# ethero_v3.net
KiCad netlist of a schematic drawn in EAGLE
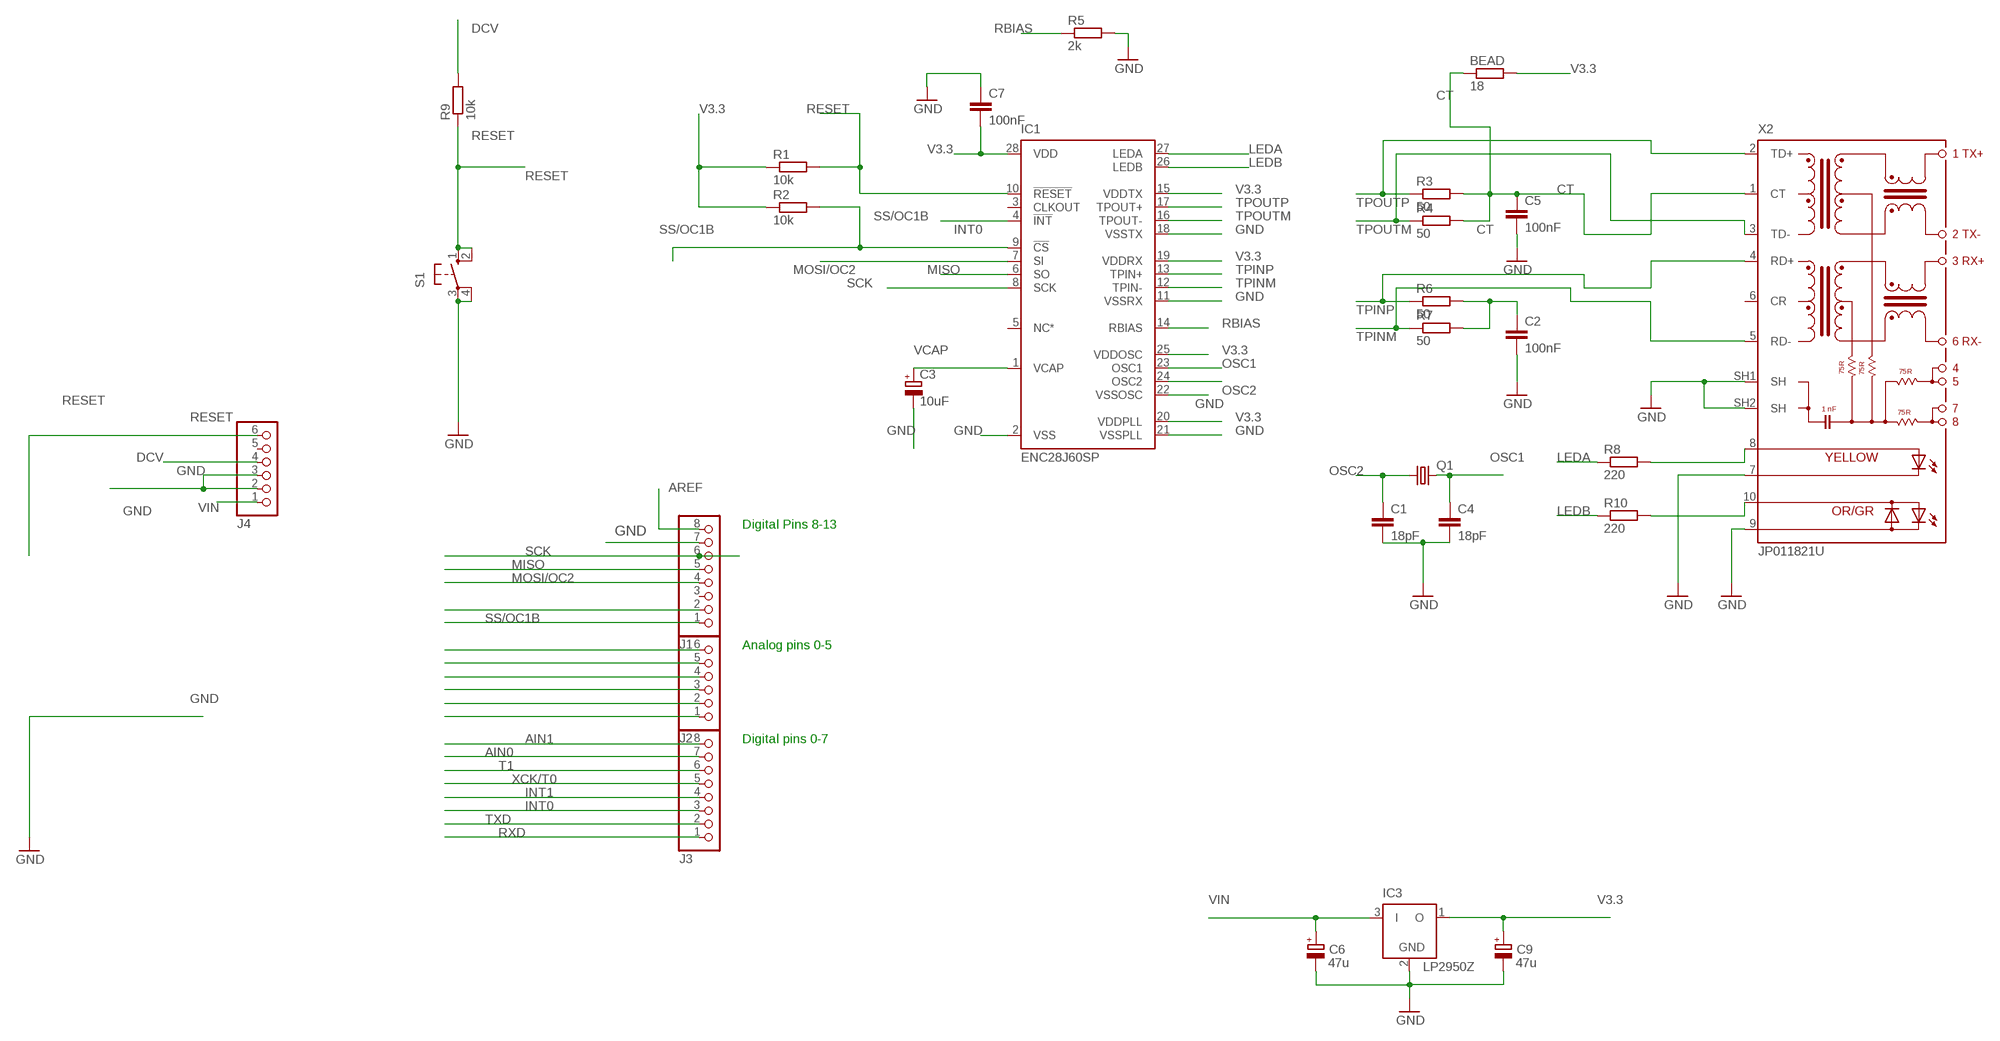
[diagram p0: schematic, sheet 1]

(export (version "E")
  (design (tool "Eeschema 10.0.6"))
  (components
    (comp (ref "BEAD")
      (value "18")
      (footprint "eagle-import:0204_7")
      (libsource (lib "eagle-import") (part "R-EU_0204/7"))
    )
    (comp (ref "C1")
      (value "18pF")
      (footprint "eagle-import:C025-025X050")
      (libsource (lib "eagle-import") (part "C-EU025-025X050"))
    )
    (comp (ref "C2")
      (value "100nF")
      (footprint "eagle-import:C025-025X050")
      (libsource (lib "eagle-import") (part "C-EU025-025X050"))
    )
    (comp (ref "C3")
      (value "10uF")
      (footprint "eagle-import:E5-5")
      (libsource (lib "eagle-import") (part "CPOL-EUE5-5"))
    )
    (comp (ref "C4")
      (value "18pF")
      (footprint "eagle-import:C025-025X050")
      (libsource (lib "eagle-import") (part "C-EU025-025X050"))
    )
    (comp (ref "C5")
      (value "100nF")
      (footprint "eagle-import:C025-025X050")
      (libsource (lib "eagle-import") (part "C-EU025-025X050"))
    )
    (comp (ref "C6")
      (value "47u")
      (footprint "eagle-import:E3,5-8")
      (libsource (lib "eagle-import") (part "CPOL-EUE3.5-8"))
    )
    (comp (ref "C7")
      (value "100nF")
      (footprint "eagle-import:C025-025X050")
      (libsource (lib "eagle-import") (part "C-EU025-025X050"))
    )
    (comp (ref "C9")
      (value "47u")
      (footprint "eagle-import:E3,5-8")
      (libsource (lib "eagle-import") (part "CPOL-EUE3.5-8"))
    )
    (comp (ref "IC1")
      (value "ENC28J60SP")
      (footprint "eagle-import:DIL28-3")
      (fields (field (name "MF") "MICROCHIP") (field (name "MPN") "ENC28J60/SP"))
      (libsource (lib "eagle-import") (part "ENC28J60SP"))
    )
    (comp (ref "IC3")
      (value "LP2950Z")
      (footprint "eagle-import:TO92")
      (libsource (lib "eagle-import") (part "LP2950Z"))
    )
    (comp (ref "J1")
      (value "PINHD-1X8")
      (footprint "eagle-import:1X08")
      (libsource (lib "eagle-import") (part "PINHD-1X8"))
    )
    (comp (ref "J2")
      (value "PINHD-1X6")
      (footprint "eagle-import:1X06")
      (libsource (lib "eagle-import") (part "PINHD-1X6"))
    )
    (comp (ref "J3")
      (value "PINHD-1X8")
      (footprint "eagle-import:1X08")
      (libsource (lib "eagle-import") (part "PINHD-1X8"))
    )
    (comp (ref "J4")
      (value "PINHD-1X6")
      (footprint "eagle-import:1X06")
      (libsource (lib "eagle-import") (part "PINHD-1X6"))
    )
    (comp (ref "Q1")
      (value "CRYSTALHC18U-V")
      (footprint "eagle-import:HC18U-V")
      (libsource (lib "eagle-import") (part "CRYSTALHC18U-V"))
    )
    (comp (ref "R1")
      (value "10k")
      (footprint "eagle-import:0204_7")
      (libsource (lib "eagle-import") (part "R-EU_0204/7"))
    )
    (comp (ref "R2")
      (value "10k")
      (footprint "eagle-import:0204_7")
      (libsource (lib "eagle-import") (part "R-EU_0204/7"))
    )
    (comp (ref "R3")
      (value "50")
      (footprint "eagle-import:0204_7")
      (libsource (lib "eagle-import") (part "R-EU_0204/7"))
    )
    (comp (ref "R4")
      (value "50")
      (footprint "eagle-import:0204_7")
      (libsource (lib "eagle-import") (part "R-EU_0204/7"))
    )
    (comp (ref "R5")
      (value "2k")
      (footprint "eagle-import:0204_7")
      (libsource (lib "eagle-import") (part "R-EU_0204/7"))
    )
    (comp (ref "R6")
      (value "50")
      (footprint "eagle-import:0204_7")
      (libsource (lib "eagle-import") (part "R-EU_0204/7"))
    )
    (comp (ref "R7")
      (value "50")
      (footprint "eagle-import:0204_7")
      (libsource (lib "eagle-import") (part "R-EU_0204/7"))
    )
    (comp (ref "R8")
      (value "220")
      (footprint "eagle-import:0204_7")
      (libsource (lib "eagle-import") (part "R-EU_0204/7"))
    )
    (comp (ref "R9")
      (value "10k")
      (footprint "eagle-import:0204_7")
      (libsource (lib "eagle-import") (part "R-EU_0204/7"))
    )
    (comp (ref "R10")
      (value "220")
      (footprint "eagle-import:0204_7")
      (libsource (lib "eagle-import") (part "R-EU_0204/7"))
    )
    (comp (ref "S1")
      (value "10-XX")
      (footprint "eagle-import:B3F-10XX")
      (fields (field (name "MPN") "B3F-1000"))
      (libsource (lib "eagle-import") (part "10-XX"))
    )
    (comp (ref "X2")
      (value "JP011821U")
      (footprint "eagle-import:JP")
      (libsource (lib "eagle-import") (part "JP011821U"))
    )
  )
  (nets
    (net (code "1") (name "/AIN0") (class "Default")
      (node (ref "J3") (pin "7") (pinfunction "7_7") (pintype "passive"))
    )
    (net (code "2") (name "/AIN1") (class "Default")
      (node (ref "J3") (pin "8") (pinfunction "8_8") (pintype "passive"))
    )
    (net (code "3") (name "/AREF") (class "Default")
      (node (ref "J1") (pin "8") (pinfunction "8_8") (pintype "passive"))
    )
    (net (code "4") (name "/CT") (class "Default")
      (node (ref "BEAD") (pin "1") (pinfunction "1_1") (pintype "passive"))
      (node (ref "C5") (pin "1") (pinfunction "1_1") (pintype "passive"))
      (node (ref "R3") (pin "2") (pinfunction "2_2") (pintype "passive"))
      (node (ref "R4") (pin "2") (pinfunction "2_2") (pintype "passive"))
      (node (ref "X2") (pin "1") (pinfunction "CT_1") (pintype "input"))
    )
    (net (code "5") (name "/DCV") (class "Default")
      (node (ref "J4") (pin "4") (pinfunction "4_4") (pintype "passive"))
      (node (ref "R9") (pin "2") (pinfunction "2_2") (pintype "passive"))
    )
    (net (code "6") (name "/INT0") (class "Default")
      (node (ref "IC1") (pin "4") (pinfunction "~{INT}_4") (pintype "output"))
      (node (ref "J3") (pin "3") (pinfunction "3_3") (pintype "passive"))
    )
    (net (code "7") (name "/INT1") (class "Default")
      (node (ref "J3") (pin "4") (pinfunction "4_4") (pintype "passive"))
    )
    (net (code "8") (name "/LEDA") (class "Default")
      (node (ref "IC1") (pin "27") (pinfunction "LEDA_27") (pintype "output"))
      (node (ref "R8") (pin "1") (pinfunction "1_1") (pintype "passive"))
    )
    (net (code "9") (name "/LEDB") (class "Default")
      (node (ref "IC1") (pin "26") (pinfunction "LEDB_26") (pintype "output"))
      (node (ref "R10") (pin "1") (pinfunction "1_1") (pintype "passive"))
    )
    (net (code "10") (name "/MISO") (class "Default")
      (node (ref "IC1") (pin "6") (pinfunction "SO_6") (pintype "output"))
      (node (ref "J1") (pin "5") (pinfunction "5_5") (pintype "passive"))
    )
    (net (code "11") (name "/MOSI{slash}OC2") (class "Default")
      (node (ref "IC1") (pin "7") (pinfunction "SI_7") (pintype "input"))
      (node (ref "J1") (pin "4") (pinfunction "4_4") (pintype "passive"))
    )
    (net (code "12") (name "/OSC1") (class "Default")
      (node (ref "C4") (pin "1") (pinfunction "1_1") (pintype "passive"))
      (node (ref "IC1") (pin "23") (pinfunction "OSC1_23") (pintype "input"))
      (node (ref "Q1") (pin "2") (pinfunction "2_2") (pintype "passive"))
    )
    (net (code "13") (name "/OSC2") (class "Default")
      (node (ref "C1") (pin "1") (pinfunction "1_1") (pintype "passive"))
      (node (ref "IC1") (pin "24") (pinfunction "OSC2_24") (pintype "output"))
      (node (ref "Q1") (pin "1") (pinfunction "1_1") (pintype "passive"))
    )
    (net (code "14") (name "/RBIAS") (class "Default")
      (node (ref "IC1") (pin "14") (pinfunction "RBIAS_14") (pintype "input"))
      (node (ref "R5") (pin "1") (pinfunction "1_1") (pintype "passive"))
    )
    (net (code "15") (name "/RESET") (class "Default")
      (node (ref "IC1") (pin "10") (pinfunction "~{RESET}_10") (pintype "input"))
      (node (ref "J4") (pin "6") (pinfunction "6_6") (pintype "passive"))
      (node (ref "R1") (pin "2") (pinfunction "2_2") (pintype "passive"))
      (node (ref "R9") (pin "1") (pinfunction "1_1") (pintype "passive"))
      (node (ref "S1") (pin "1") (pinfunction "S_1") (pintype "passive"))
      (node (ref "S1") (pin "2") (pinfunction "S1_2") (pintype "passive"))
    )
    (net (code "16") (name "/RXD") (class "Default")
      (node (ref "J3") (pin "1") (pinfunction "1_1") (pintype "passive"))
    )
    (net (code "17") (name "/SCK") (class "Default")
      (node (ref "IC1") (pin "8") (pinfunction "SCK_8") (pintype "input"))
      (node (ref "J1") (pin "6") (pinfunction "6_6") (pintype "passive"))
    )
    (net (code "18") (name "/SS{slash}OC1B") (class "Default")
      (node (ref "IC1") (pin "9") (pinfunction "~{CS}_9") (pintype "input"))
      (node (ref "J1") (pin "1") (pinfunction "1_1") (pintype "passive"))
      (node (ref "R2") (pin "2") (pinfunction "2_2") (pintype "passive"))
    )
    (net (code "19") (name "/T1") (class "Default")
      (node (ref "J3") (pin "6") (pinfunction "6_6") (pintype "passive"))
    )
    (net (code "20") (name "/TPINM") (class "Default")
      (node (ref "IC1") (pin "12") (pinfunction "TPIN-_12") (pintype "input"))
      (node (ref "R7") (pin "1") (pinfunction "1_1") (pintype "passive"))
      (node (ref "X2") (pin "5") (pinfunction "RD-_5") (pintype "input"))
    )
    (net (code "21") (name "/TPINP") (class "Default")
      (node (ref "IC1") (pin "13") (pinfunction "TPIN+_13") (pintype "input"))
      (node (ref "R6") (pin "1") (pinfunction "1_1") (pintype "passive"))
      (node (ref "X2") (pin "4") (pinfunction "RD+_4") (pintype "input"))
    )
    (net (code "22") (name "/TPOUTM") (class "Default")
      (node (ref "IC1") (pin "16") (pinfunction "TPOUT-_16") (pintype "output"))
      (node (ref "R4") (pin "1") (pinfunction "1_1") (pintype "passive"))
      (node (ref "X2") (pin "3") (pinfunction "TD-_3") (pintype "input"))
    )
    (net (code "23") (name "/TPOUTP") (class "Default")
      (node (ref "IC1") (pin "17") (pinfunction "TPOUT+_17") (pintype "output"))
      (node (ref "R3") (pin "1") (pinfunction "1_1") (pintype "passive"))
      (node (ref "X2") (pin "2") (pinfunction "TD+_2") (pintype "input"))
    )
    (net (code "24") (name "/TXD") (class "Default")
      (node (ref "J3") (pin "2") (pinfunction "2_2") (pintype "passive"))
    )
    (net (code "25") (name "/V3.3") (class "Default")
      (node (ref "BEAD") (pin "2") (pinfunction "2_2") (pintype "passive"))
      (node (ref "C7") (pin "2") (pinfunction "2_2") (pintype "passive"))
      (node (ref "C9") (pin "+") (pinfunction "+_+") (pintype "passive"))
      (node (ref "IC1") (pin "15") (pinfunction "VDDTX_15") (pintype "input"))
      (node (ref "IC1") (pin "19") (pinfunction "VDDRX_19") (pintype "input"))
      (node (ref "IC1") (pin "20") (pinfunction "VDDPLL_20") (pintype "input"))
      (node (ref "IC1") (pin "25") (pinfunction "VDDOSC_25") (pintype "input"))
      (node (ref "IC1") (pin "28") (pinfunction "VDD_28") (pintype "input"))
      (node (ref "IC3") (pin "1") (pinfunction "O_1") (pintype "input"))
      (node (ref "R1") (pin "1") (pinfunction "1_1") (pintype "passive"))
      (node (ref "R2") (pin "1") (pinfunction "1_1") (pintype "passive"))
    )
    (net (code "26") (name "/VCAP") (class "Default")
      (node (ref "C3") (pin "+") (pinfunction "+_+") (pintype "passive"))
      (node (ref "IC1") (pin "1") (pinfunction "VCAP_1") (pintype "input"))
    )
    (net (code "27") (name "/VIN") (class "Default")
      (node (ref "C6") (pin "+") (pinfunction "+_+") (pintype "passive"))
      (node (ref "IC3") (pin "3") (pinfunction "I_3") (pintype "input"))
      (node (ref "J4") (pin "1") (pinfunction "1_1") (pintype "passive"))
    )
    (net (code "28") (name "/XCK{slash}T0") (class "Default")
      (node (ref "J3") (pin "5") (pinfunction "5_5") (pintype "passive"))
    )
    (net (code "29") (name "GND") (class "Default")
      (node (ref "C1") (pin "2") (pinfunction "2_2") (pintype "passive"))
      (node (ref "C2") (pin "2") (pinfunction "2_2") (pintype "passive"))
      (node (ref "C3") (pin "-") (pinfunction "-_-") (pintype "passive"))
      (node (ref "C4") (pin "2") (pinfunction "2_2") (pintype "passive"))
      (node (ref "C5") (pin "2") (pinfunction "2_2") (pintype "passive"))
      (node (ref "C6") (pin "-") (pinfunction "-_-") (pintype "passive"))
      (node (ref "C7") (pin "1") (pinfunction "1_1") (pintype "passive"))
      (node (ref "C9") (pin "-") (pinfunction "-_-") (pintype "passive"))
      (node (ref "IC1") (pin "11") (pinfunction "VSSRX_11") (pintype "input"))
      (node (ref "IC1") (pin "18") (pinfunction "VSSTX_18") (pintype "input"))
      (node (ref "IC1") (pin "2") (pinfunction "VSS_2") (pintype "input"))
      (node (ref "IC1") (pin "21") (pinfunction "VSSPLL_21") (pintype "input"))
      (node (ref "IC1") (pin "22") (pinfunction "VSSOSC_22") (pintype "input"))
      (node (ref "IC3") (pin "2") (pinfunction "GND_2") (pintype "power_in"))
      (node (ref "J1") (pin "7") (pinfunction "7_7") (pintype "passive"))
      (node (ref "J4") (pin "2") (pinfunction "2_2") (pintype "passive"))
      (node (ref "J4") (pin "3") (pinfunction "3_3") (pintype "passive"))
      (node (ref "R5") (pin "2") (pinfunction "2_2") (pintype "passive"))
      (node (ref "S1") (pin "3") (pinfunction "P_3") (pintype "passive"))
      (node (ref "S1") (pin "4") (pinfunction "P1_4") (pintype "passive"))
      (node (ref "X2") (pin "7") (pinfunction "C-Y_7") (pintype "input"))
      (node (ref "X2") (pin "9") (pinfunction "A-O_C-G_9") (pintype "input"))
      (node (ref "X2") (pin "SH1") (pinfunction "SH_SH1") (pintype "input"))
      (node (ref "X2") (pin "SH2") (pinfunction "SH_SH2") (pintype "input"))
    )
    (net (code "30") (name "Net-(C2-Pad1)") (class "Default")
      (node (ref "C2") (pin "1") (pinfunction "1_1") (pintype "passive"))
      (node (ref "R6") (pin "2") (pinfunction "2_2") (pintype "passive"))
      (node (ref "R7") (pin "2") (pinfunction "2_2") (pintype "passive"))
    )
    (net (code "31") (name "Net-(X2-A-Y)") (class "Default")
      (node (ref "R8") (pin "2") (pinfunction "2_2") (pintype "passive"))
      (node (ref "X2") (pin "8") (pinfunction "A-Y_8") (pintype "input"))
    )
    (net (code "32") (name "Net-(X2-C-O_A-G)") (class "Default")
      (node (ref "R10") (pin "2") (pinfunction "2_2") (pintype "passive"))
      (node (ref "X2") (pin "10") (pinfunction "C-O_A-G_10") (pintype "input"))
    )
    (net (code "33") (name "unconnected-(IC1-CLKOUT-Pad3)") (class "Default")
      (node (ref "IC1") (pin "3") (pinfunction "CLKOUT_3") (pintype "output"))
    )
    (net (code "34") (name "unconnected-(IC1-NC*-Pad5)") (class "Default")
      (node (ref "IC1") (pin "5") (pinfunction "NC*_5") (pintype "output"))
    )
    (net (code "35") (name "unconnected-(J1-Pad2)") (class "Default")
      (node (ref "J1") (pin "2") (pinfunction "2_2") (pintype "passive"))
    )
    (net (code "36") (name "unconnected-(J1-Pad3)") (class "Default")
      (node (ref "J1") (pin "3") (pinfunction "3_3") (pintype "passive"))
    )
    (net (code "37") (name "unconnected-(J2-Pad1)") (class "Default")
      (node (ref "J2") (pin "1") (pinfunction "1_1") (pintype "passive"))
    )
    (net (code "38") (name "unconnected-(J2-Pad2)") (class "Default")
      (node (ref "J2") (pin "2") (pinfunction "2_2") (pintype "passive"))
    )
    (net (code "39") (name "unconnected-(J2-Pad3)") (class "Default")
      (node (ref "J2") (pin "3") (pinfunction "3_3") (pintype "passive"))
    )
    (net (code "40") (name "unconnected-(J2-Pad4)") (class "Default")
      (node (ref "J2") (pin "4") (pinfunction "4_4") (pintype "passive"))
    )
    (net (code "41") (name "unconnected-(J2-Pad5)") (class "Default")
      (node (ref "J2") (pin "5") (pinfunction "5_5") (pintype "passive"))
    )
    (net (code "42") (name "unconnected-(J2-Pad6)") (class "Default")
      (node (ref "J2") (pin "6") (pinfunction "6_6") (pintype "passive"))
    )
    (net (code "43") (name "unconnected-(J4-Pad5)") (class "Default")
      (node (ref "J4") (pin "5") (pinfunction "5_5") (pintype "passive"))
    )
    (net (code "44") (name "unconnected-(X2-CR-Pad6)") (class "Default")
      (node (ref "X2") (pin "6") (pinfunction "CR_6") (pintype "input"))
    )
  )
)
